# Safe_Cracker_ShieldEDITED.net
KiCad netlist of a schematic drawn in EAGLE
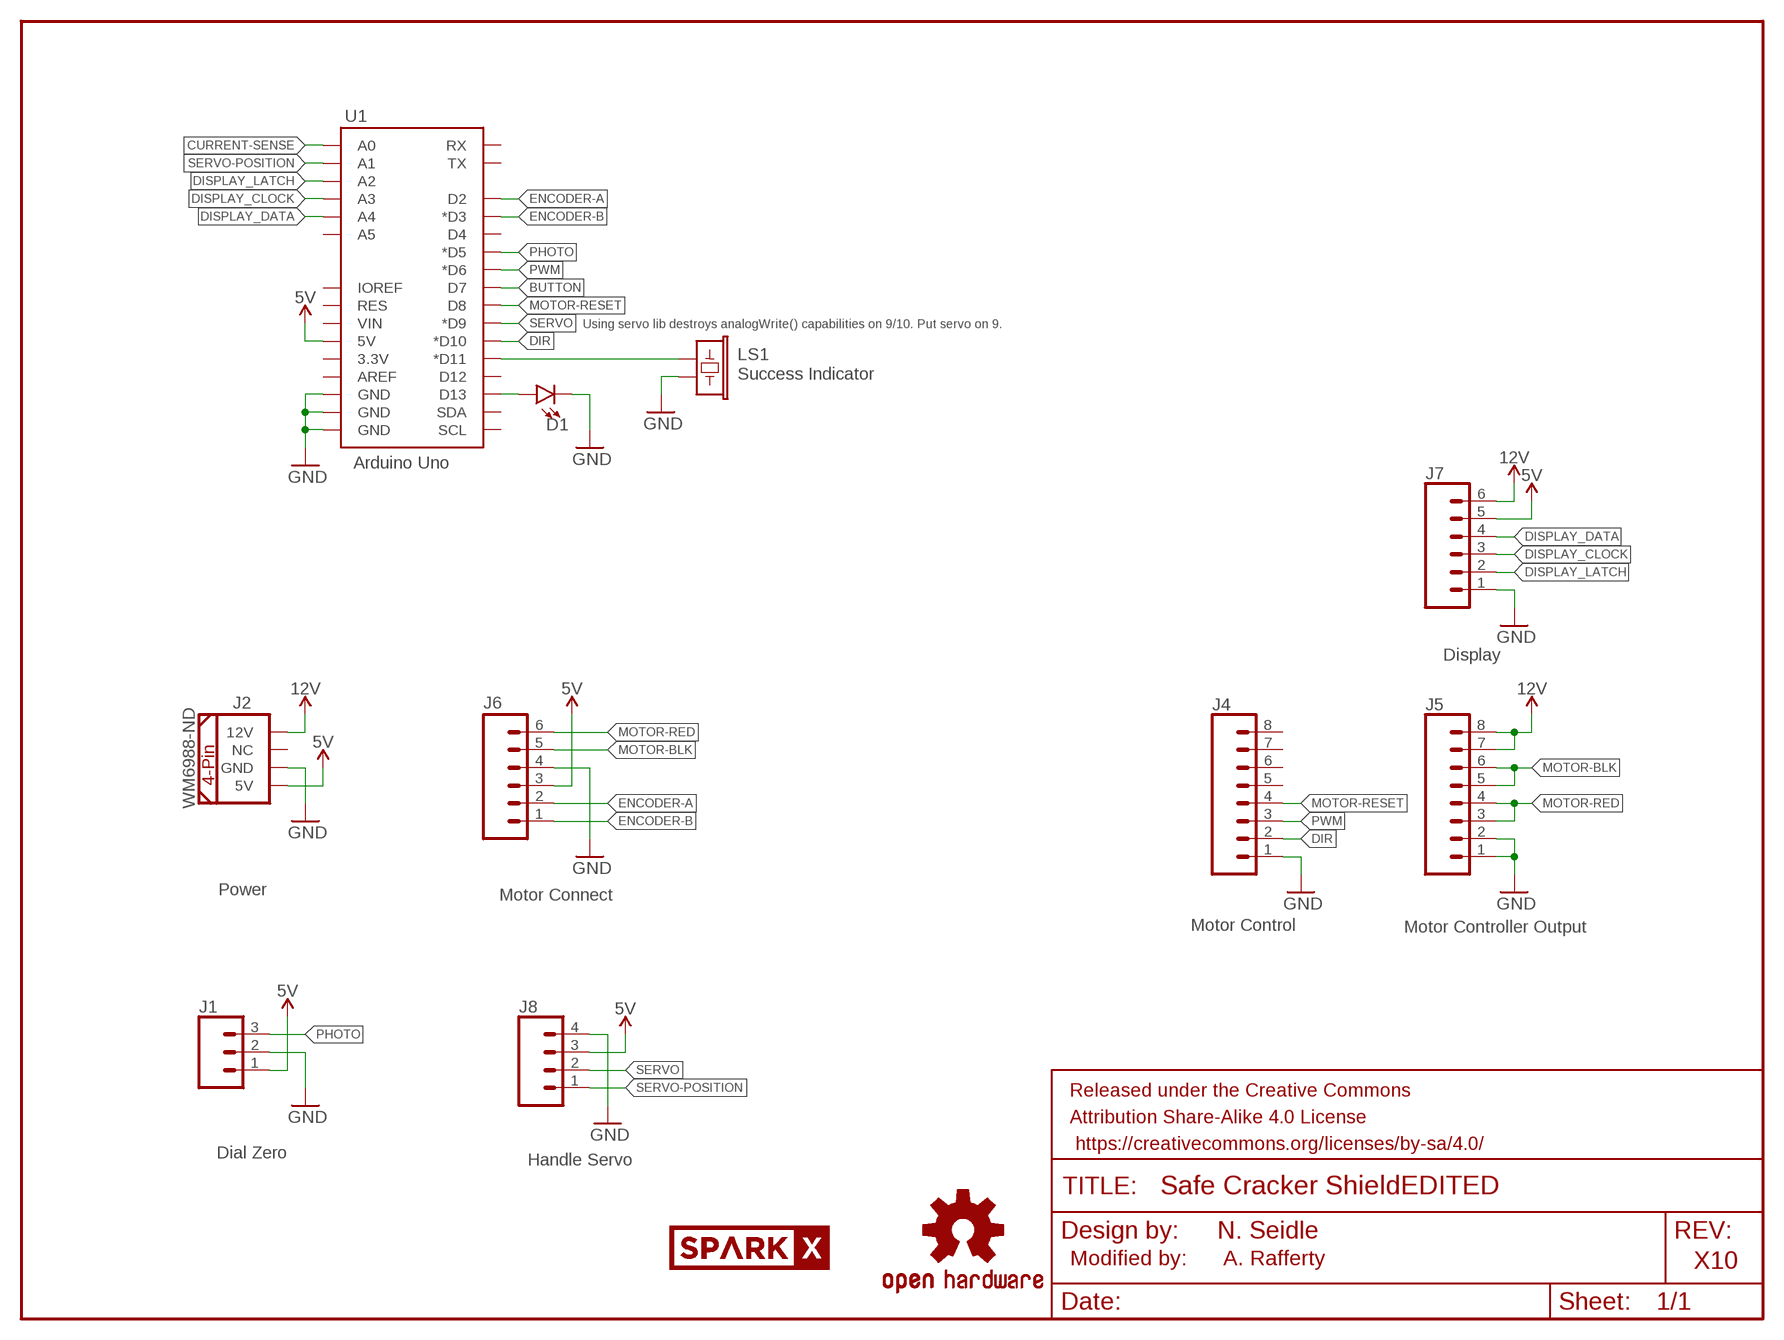
[diagram p0: schematic, sheet 1]

(export (version "E")
  (design (tool "Eeschema 10.0.6"))
  (components
    (comp (ref "D1")
      (value "LED5MM")
      (footprint "eagle-import:LED_5MM")
      (libsource (lib "eagle-import") (part "LED5MM"))
    )
    (comp (ref "FRAME1")
      (value "FRAME-LETTER")
      (footprint "eagle-import:CREATIVE_COMMONS")
      (libsource (lib "eagle-import") (part "FRAME-LETTER"))
    )
    (comp (ref "J1")
      (value "CONN_03JST-PTH-VERT")
      (footprint "eagle-import:JST-3-PTH-VERT")
      (libsource (lib "eagle-import") (part "CONN_03JST-PTH-VERT"))
    )
    (comp (ref "J2")
      (value "Power")
      (footprint "eagle-import:COMPUTER-PERIPHERAL-POWER-RA")
      (libsource (lib "eagle-import") (part "COMPUTER-PERIPHERAL-POWERRA"))
    )
    (comp (ref "J4")
      (value "Motor Control")
      (footprint "eagle-import:1X08")
      (libsource (lib "eagle-import") (part "CONN_08{dblquote}"))
    )
    (comp (ref "J5")
      (value "Motor Controller Output")
      (footprint "eagle-import:1X08")
      (libsource (lib "eagle-import") (part "CONN_08{dblquote}"))
    )
    (comp (ref "J6")
      (value "Motor Connect")
      (footprint "eagle-import:1X06@1")
      (libsource (lib "eagle-import") (part "M06SILK_FEMALE_PTH"))
    )
    (comp (ref "J7")
      (value "CONN_06SILK_FEMALE_PTH")
      (footprint "eagle-import:1X06")
      (libsource (lib "eagle-import") (part "CONN_06SILK_FEMALE_PTH"))
    )
    (comp (ref "J8")
      (value "Handle Servo")
      (footprint "eagle-import:1X04")
      (libsource (lib "eagle-import") (part "CONN_04"))
    )
    (comp (ref "LOGO2")
      (value "OSHW-LOGOS")
      (footprint "eagle-import:OSHW-LOGO-S")
      (libsource (lib "eagle-import") (part "OSHW-LOGOS"))
    )
    (comp (ref "LS1")
      (value "Success Indicator")
      (footprint "eagle-import:BUZZER-12MM")
      (libsource (lib "eagle-import") (part "BUZZER-PTH"))
    )
    (comp (ref "U$1")
      (value "SPARKX-LOGO5")
      (footprint "eagle-import:SPARKX-LARGE")
      (libsource (lib "eagle-import") (part "SPARKX-LOGO5"))
    )
    (comp (ref "U1")
      (value "Arduino Uno")
      (footprint "eagle-import:UNO_R3_SHIELD_NOLABELS")
      (libsource (lib "eagle-import") (part "ARDUINO_R3_SHIELDNOLABELS"))
    )
  )
  (nets
    (net (code "1") (name "5V") (class "Default")
      (node (ref "J1") (pin "1") (pinfunction "1_1") (pintype "passive"))
      (node (ref "J2") (pin "5V") (pinfunction "5V_5V") (pintype "passive"))
      (node (ref "J6") (pin "3") (pinfunction "3_3") (pintype "passive"))
      (node (ref "J7") (pin "5") (pinfunction "5_5") (pintype "passive"))
      (node (ref "J8") (pin "3") (pinfunction "3_3") (pintype "passive"))
      (node (ref "U1") (pin "5V") (pinfunction "5V_5V") (pintype "bidirectional"))
    )
    (net (code "2") (name "12V") (class "Default")
      (node (ref "J2") (pin "12V") (pinfunction "12V_12V") (pintype "passive"))
      (node (ref "J5") (pin "7") (pinfunction "7_7") (pintype "passive"))
      (node (ref "J5") (pin "8") (pinfunction "8_8") (pintype "passive"))
      (node (ref "J7") (pin "6") (pinfunction "6_6") (pintype "passive"))
    )
    (net (code "3") (name "BUTTON") (class "Default")
      (node (ref "U1") (pin "D7") (pinfunction "D7_D7") (pintype "bidirectional"))
    )
    (net (code "4") (name "CURRENT-SENSE") (class "Default")
      (node (ref "U1") (pin "A0") (pinfunction "A0_A0") (pintype "bidirectional"))
    )
    (net (code "5") (name "DIR") (class "Default")
      (node (ref "J4") (pin "2") (pinfunction "2_2") (pintype "passive"))
      (node (ref "U1") (pin "D10") (pinfunction "*D10_D10") (pintype "bidirectional"))
    )
    (net (code "6") (name "DISPLAY_CLOCK") (class "Default")
      (node (ref "J7") (pin "3") (pinfunction "3_3") (pintype "passive"))
      (node (ref "U1") (pin "A3") (pinfunction "A3_A3") (pintype "bidirectional"))
    )
    (net (code "7") (name "DISPLAY_DATA") (class "Default")
      (node (ref "J7") (pin "4") (pinfunction "4_4") (pintype "passive"))
      (node (ref "U1") (pin "A4") (pinfunction "A4_A4") (pintype "bidirectional"))
    )
    (net (code "8") (name "DISPLAY_LATCH") (class "Default")
      (node (ref "J7") (pin "2") (pinfunction "2_2") (pintype "passive"))
      (node (ref "U1") (pin "A2") (pinfunction "A2_A2") (pintype "bidirectional"))
    )
    (net (code "9") (name "ENCODER-A") (class "Default")
      (node (ref "J6") (pin "2") (pinfunction "2_2") (pintype "passive"))
      (node (ref "U1") (pin "D2") (pinfunction "D2_D2") (pintype "bidirectional"))
    )
    (net (code "10") (name "ENCODER-B") (class "Default")
      (node (ref "J6") (pin "1") (pinfunction "1_1") (pintype "passive"))
      (node (ref "U1") (pin "D3") (pinfunction "*D3_D3") (pintype "bidirectional"))
    )
    (net (code "11") (name "GND") (class "Default")
      (node (ref "D1") (pin "K") (pinfunction "C_K") (pintype "passive"))
      (node (ref "J1") (pin "2") (pinfunction "2_2") (pintype "passive"))
      (node (ref "J2") (pin "GND") (pinfunction "GND_GND") (pintype "passive"))
      (node (ref "J4") (pin "1") (pinfunction "1_1") (pintype "passive"))
      (node (ref "J5") (pin "1") (pinfunction "1_1") (pintype "passive"))
      (node (ref "J5") (pin "2") (pinfunction "2_2") (pintype "passive"))
      (node (ref "J6") (pin "4") (pinfunction "4_4") (pintype "passive"))
      (node (ref "J7") (pin "1") (pinfunction "1_1") (pintype "passive"))
      (node (ref "J8") (pin "4") (pinfunction "4_4") (pintype "passive"))
      (node (ref "LS1") (pin "-") (pinfunction "2_-") (pintype "passive"))
      (node (ref "U1") (pin "GND@0") (pinfunction "GND_GND@0") (pintype "bidirectional"))
      (node (ref "U1") (pin "GND@1") (pinfunction "GND_GND@1") (pintype "bidirectional"))
      (node (ref "U1") (pin "GND@2") (pinfunction "GND_GND@2") (pintype "bidirectional"))
    )
    (net (code "12") (name "MOTOR-BLK") (class "Default")
      (node (ref "J5") (pin "5") (pinfunction "5_5") (pintype "passive"))
      (node (ref "J5") (pin "6") (pinfunction "6_6") (pintype "passive"))
      (node (ref "J6") (pin "5") (pinfunction "5_5") (pintype "passive"))
    )
    (net (code "13") (name "MOTOR-RED") (class "Default")
      (node (ref "J5") (pin "3") (pinfunction "3_3") (pintype "passive"))
      (node (ref "J5") (pin "4") (pinfunction "4_4") (pintype "passive"))
      (node (ref "J6") (pin "6") (pinfunction "6_6") (pintype "passive"))
    )
    (net (code "14") (name "MOTOR-RESET") (class "Default")
      (node (ref "J4") (pin "4") (pinfunction "4_4") (pintype "passive"))
      (node (ref "U1") (pin "D8") (pinfunction "D8_D8") (pintype "bidirectional"))
    )
    (net (code "15") (name "Net-(D1-PadA)") (class "Default")
      (node (ref "D1") (pin "A") (pinfunction "A_A") (pintype "passive"))
      (node (ref "U1") (pin "D13") (pinfunction "D13_D13") (pintype "bidirectional"))
    )
    (net (code "16") (name "Net-(LS1-1)") (class "Default")
      (node (ref "LS1") (pin "+") (pinfunction "1_+") (pintype "passive"))
      (node (ref "U1") (pin "D11") (pinfunction "*D11_D11") (pintype "bidirectional"))
    )
    (net (code "17") (name "PHOTO") (class "Default")
      (node (ref "J1") (pin "3") (pinfunction "3_3") (pintype "passive"))
      (node (ref "U1") (pin "D5") (pinfunction "*D5_D5") (pintype "bidirectional"))
    )
    (net (code "18") (name "PWM") (class "Default")
      (node (ref "J4") (pin "3") (pinfunction "3_3") (pintype "passive"))
      (node (ref "U1") (pin "D6") (pinfunction "*D6_D6") (pintype "bidirectional"))
    )
    (net (code "19") (name "SERVO") (class "Default")
      (node (ref "J8") (pin "2") (pinfunction "2_2") (pintype "passive"))
      (node (ref "U1") (pin "D9") (pinfunction "*D9_D9") (pintype "bidirectional"))
    )
    (net (code "20") (name "SERVO-POSITION") (class "Default")
      (node (ref "J8") (pin "1") (pinfunction "1_1") (pintype "passive"))
      (node (ref "U1") (pin "A1") (pinfunction "A1_A1") (pintype "bidirectional"))
    )
    (net (code "21") (name "unconnected-(J2-PadNC)") (class "Default")
      (node (ref "J2") (pin "NC") (pinfunction "NC_NC") (pintype "passive"))
    )
    (net (code "22") (name "unconnected-(J4-Pad5)") (class "Default")
      (node (ref "J4") (pin "5") (pinfunction "5_5") (pintype "passive"))
    )
    (net (code "23") (name "unconnected-(J4-Pad6)") (class "Default")
      (node (ref "J4") (pin "6") (pinfunction "6_6") (pintype "passive"))
    )
    (net (code "24") (name "unconnected-(J4-Pad7)") (class "Default")
      (node (ref "J4") (pin "7") (pinfunction "7_7") (pintype "passive"))
    )
    (net (code "25") (name "unconnected-(J4-Pad8)") (class "Default")
      (node (ref "J4") (pin "8") (pinfunction "8_8") (pintype "passive"))
    )
    (net (code "26") (name "unconnected-(U1-Pad3.3V)") (class "Default")
      (node (ref "U1") (pin "3.3V") (pinfunction "3.3V_3.3V") (pintype "bidirectional"))
    )
    (net (code "27") (name "unconnected-(U1-PadA5)") (class "Default")
      (node (ref "U1") (pin "A5") (pinfunction "A5_A5") (pintype "bidirectional"))
    )
    (net (code "28") (name "unconnected-(U1-PadAREF)") (class "Default")
      (node (ref "U1") (pin "AREF") (pinfunction "AREF_AREF") (pintype "bidirectional"))
    )
    (net (code "29") (name "unconnected-(U1-PadD4)") (class "Default")
      (node (ref "U1") (pin "D4") (pinfunction "D4_D4") (pintype "bidirectional"))
    )
    (net (code "30") (name "unconnected-(U1-PadD12)") (class "Default")
      (node (ref "U1") (pin "D12") (pinfunction "D12_D12") (pintype "bidirectional"))
    )
    (net (code "31") (name "unconnected-(U1-PadIOREF)") (class "Default")
      (node (ref "U1") (pin "IOREF") (pinfunction "IOREF_IOREF") (pintype "bidirectional"))
    )
    (net (code "32") (name "unconnected-(U1-PadRES)") (class "Default")
      (node (ref "U1") (pin "RES") (pinfunction "RES_RES") (pintype "bidirectional"))
    )
    (net (code "33") (name "unconnected-(U1-PadRX)") (class "Default")
      (node (ref "U1") (pin "RX") (pinfunction "RX_RX") (pintype "bidirectional"))
    )
    (net (code "34") (name "unconnected-(U1-PadSCL)") (class "Default")
      (node (ref "U1") (pin "SCL") (pinfunction "SCL_SCL") (pintype "bidirectional"))
    )
    (net (code "35") (name "unconnected-(U1-PadSDA)") (class "Default")
      (node (ref "U1") (pin "SDA") (pinfunction "SDA_SDA") (pintype "bidirectional"))
    )
    (net (code "36") (name "unconnected-(U1-PadTX)") (class "Default")
      (node (ref "U1") (pin "TX") (pinfunction "TX_TX") (pintype "bidirectional"))
    )
    (net (code "37") (name "unconnected-(U1-PadVIN)") (class "Default")
      (node (ref "U1") (pin "VIN") (pinfunction "VIN_VIN") (pintype "bidirectional"))
    )
  )
)
